# M6_GPOI_V4_1_after_labelling.net
KiCad netlist of a schematic drawn in EAGLE
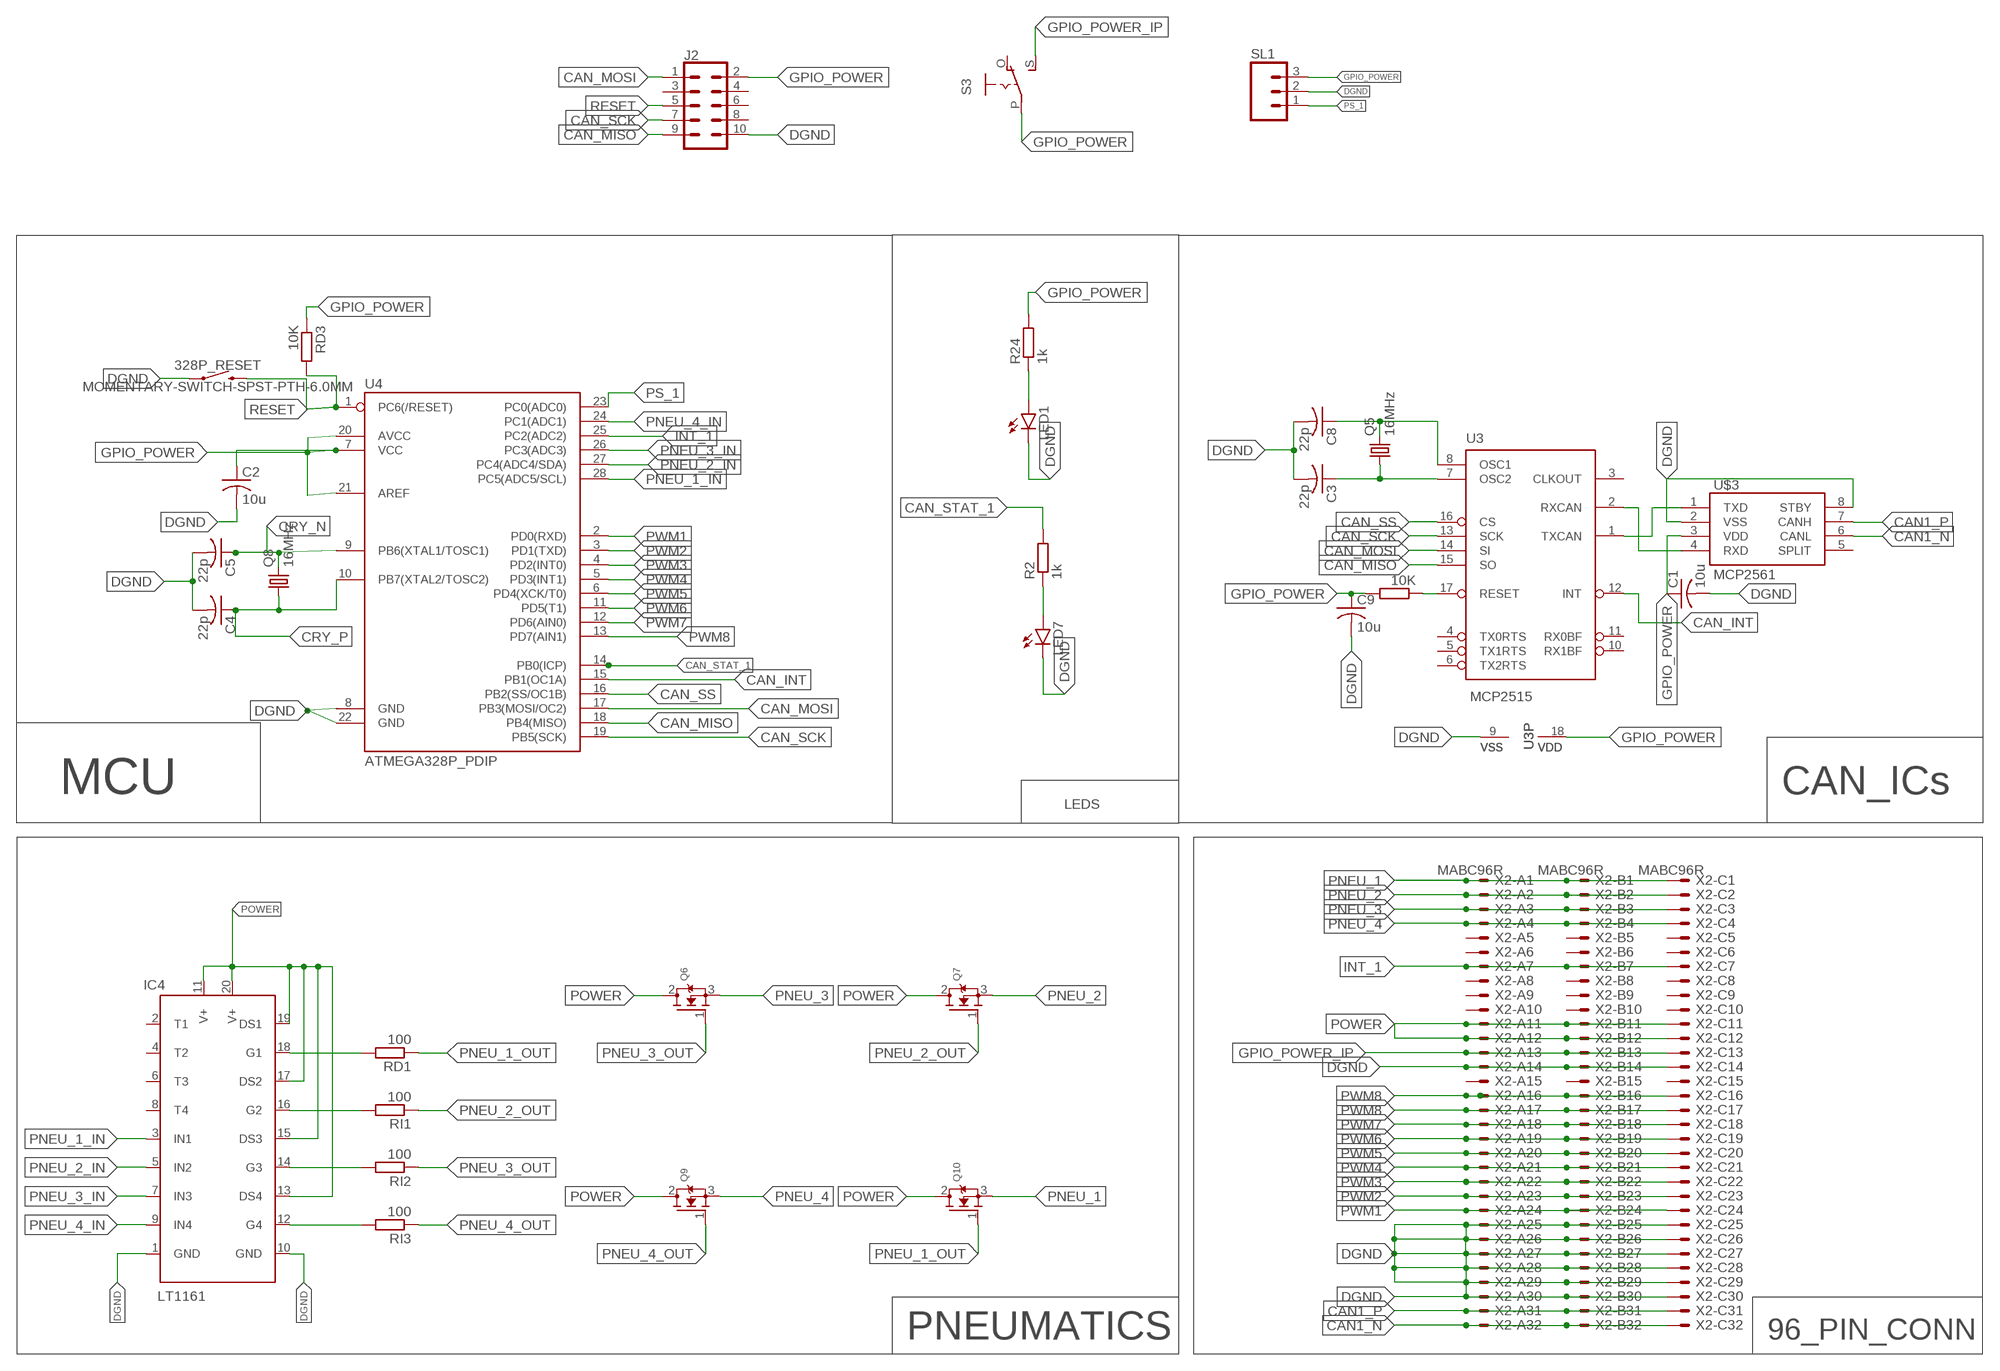
[diagram p0: schematic, sheet 1]

(export (version "E")
  (design (tool "Eeschema 10.0.6"))
  (components
    (comp (ref "328P_RESET")
      (value "MOMENTARY-SWITCH-SPST-PTH-6.0MM")
      (footprint "eagle-import:TACTILE_SWITCH_PTH_6.0MM")
      (libsource (lib "eagle-import") (part "MOMENTARY-SWITCH-SPST-PTH-6.0MM"))
    )
    (comp (ref "C1")
      (value "10u")
      (footprint "eagle-import:C025-050X050")
      (libsource (lib "eagle-import") (part "C-US025-050X050"))
    )
    (comp (ref "C2")
      (value "10u")
      (footprint "eagle-import:C025-050X050")
      (libsource (lib "eagle-import") (part "C-US025-050X050"))
    )
    (comp (ref "C3")
      (value "22p")
      (footprint "eagle-import:C025-024X044")
      (libsource (lib "eagle-import") (part "resistor_C-US025-024X044"))
    )
    (comp (ref "C4")
      (value "22p")
      (footprint "eagle-import:C025-024X044")
      (libsource (lib "eagle-import") (part "resistor_348_C-US025-024X044"))
    )
    (comp (ref "C5")
      (value "22p")
      (footprint "eagle-import:C025-024X044")
      (libsource (lib "eagle-import") (part "resistor_348_C-US025-024X044"))
    )
    (comp (ref "C8")
      (value "22p")
      (footprint "eagle-import:C025-024X044")
      (libsource (lib "eagle-import") (part "resistor_C-US025-024X044"))
    )
    (comp (ref "C9")
      (value "10u")
      (footprint "eagle-import:C025-050X050")
      (libsource (lib "eagle-import") (part "C-US025-050X050"))
    )
    (comp (ref "IC4")
      (value "LT1161")
      (footprint "eagle-import:ROBOSUB_LINEAR-TECHNOLOGY_LT1161_QUAD-HIGH-SIDE-MOSFET-DRIVER_SO20")
      (fields (field (name "MF") "INTERSIL") (field (name "MPN") "HIP4086ABZ"))
      (libsource (lib "eagle-import") (part "ROBOSUB_LINEAR-TECHNOLOGY_LT1161_QUAD-HIGH-SIDE-MOSFET-DRIVER_LT1161-SO20SW"))
    )
    (comp (ref "J2")
      (value "CONN_05X2SHD")
      (footprint "eagle-import:2X5-SHROUDED")
      (libsource (lib "eagle-import") (part "CONN_05X2SHD"))
    )
    (comp (ref "LED1")
      (value "LEDCHIPLED_0805")
      (footprint "eagle-import:CHIPLED_0805")
      (libsource (lib "eagle-import") (part "LEDCHIPLED_0805"))
    )
    (comp (ref "LED7")
      (value "LEDCHIPLED_0805")
      (footprint "eagle-import:CHIPLED_0805")
      (libsource (lib "eagle-import") (part "LEDCHIPLED_0805"))
    )
    (comp (ref "Q5")
      (value "16MHz")
      (footprint "eagle-import:HC49_S")
      (libsource (lib "eagle-import") (part "CRYSTALHC49S"))
    )
    (comp (ref "Q6")
      (value "MOSFET-NGDS_TO220V")
      (footprint "eagle-import:TO220V")
      (libsource (lib "eagle-import") (part "MOSFET-NGDS_TO220V"))
    )
    (comp (ref "Q7")
      (value "MOSFET-NGDS_TO220V")
      (footprint "eagle-import:TO220V")
      (libsource (lib "eagle-import") (part "MOSFET-NGDS_TO220V"))
    )
    (comp (ref "Q8")
      (value "16MHz")
      (footprint "eagle-import:HC49_S")
      (libsource (lib "eagle-import") (part "CRYSTALHC49S"))
    )
    (comp (ref "Q9")
      (value "MOSFET-NGDS_TO220V")
      (footprint "eagle-import:TO220V")
      (libsource (lib "eagle-import") (part "MOSFET-NGDS_TO220V"))
    )
    (comp (ref "Q10")
      (value "MOSFET-NGDS_TO220V")
      (footprint "eagle-import:TO220V")
      (libsource (lib "eagle-import") (part "MOSFET-NGDS_TO220V"))
    )
    (comp (ref "R2")
      (value "1k")
      (footprint "eagle-import:M0805")
      (libsource (lib "eagle-import") (part "R-EU_M0805"))
    )
    (comp (ref "R24")
      (value "1k")
      (footprint "eagle-import:M0805")
      (libsource (lib "eagle-import") (part "R-EU_M0805"))
    )
    (comp (ref "RD1")
      (value "100")
      (footprint "eagle-import:M0805")
      (libsource (lib "eagle-import") (part "R-EU_M0805"))
    )
    (comp (ref "RD2")
      (value "10K")
      (footprint "eagle-import:M0805")
      (libsource (lib "eagle-import") (part "R-EU_M0805"))
    )
    (comp (ref "RD3")
      (value "10K")
      (footprint "eagle-import:M0805")
      (libsource (lib "eagle-import") (part "R-EU_M0805"))
    )
    (comp (ref "RI1")
      (value "100")
      (footprint "eagle-import:M0805")
      (libsource (lib "eagle-import") (part "R-EU_M0805"))
    )
    (comp (ref "RI2")
      (value "100")
      (footprint "eagle-import:M0805")
      (libsource (lib "eagle-import") (part "R-EU_M0805"))
    )
    (comp (ref "RI3")
      (value "100")
      (footprint "eagle-import:M0805")
      (libsource (lib "eagle-import") (part "R-EU_M0805"))
    )
    (comp (ref "S3")
      (value "EG1218S")
      (footprint "eagle-import:EG1218")
      (libsource (lib "eagle-import") (part "EG1218S"))
    )
    (comp (ref "SL1")
      (value "MA03")
      (footprint "eagle-import:03P")
      (libsource (lib "eagle-import") (part "MA03"))
    )
    (comp (ref "U$3")
      (value "MCP2561")
      (footprint "eagle-import:DIP08")
      (libsource (lib "eagle-import") (part "MCP2561"))
    )
    (comp (ref "U3")
      (value "MCP2515")
      (footprint "eagle-import:DIP18")
      (libsource (lib "eagle-import") (part "MCP2515(MCP2510)P"))
    )
    (comp (ref "U4")
      (value "ATMEGA328P_PDIP")
      (footprint "eagle-import:DIL28-3")
      (libsource (lib "eagle-import") (part "ATMEGA328P_PDIP"))
    )
    (comp (ref "X2")
      (value "MABC96R")
      (footprint "eagle-import:MABC96R")
      (fields (field (name "OC_FARNELL") "unknown"))
      (libsource (lib "eagle-import") (part "MABC96R"))
    )
  )
  (nets
    (net (code "1") (name "CAN1_N") (class "Default")
      (node (ref "U$3") (pin "6") (pinfunction "CANL_6") (pintype "bidirectional"))
      (node (ref "X2") (pin "A32") (pinfunction "S_A32") (pintype "passive"))
      (node (ref "X2") (pin "B32") (pinfunction "S_B32") (pintype "passive"))
      (node (ref "X2") (pin "C32") (pinfunction "S_C32") (pintype "passive"))
    )
    (net (code "2") (name "CAN1_P") (class "Default")
      (node (ref "U$3") (pin "7") (pinfunction "CANH_7") (pintype "bidirectional"))
      (node (ref "X2") (pin "A31") (pinfunction "S_A31") (pintype "passive"))
      (node (ref "X2") (pin "B31") (pinfunction "S_B31") (pintype "passive"))
      (node (ref "X2") (pin "C31") (pinfunction "S_C31") (pintype "passive"))
    )
    (net (code "3") (name "CAN_INT") (class "Default")
      (node (ref "U3") (pin "12") (pinfunction "INT_12") (pintype "output"))
      (node (ref "U4") (pin "15") (pinfunction "PB1(OC1A)_15") (pintype "bidirectional"))
    )
    (net (code "4") (name "CAN_MISO") (class "Default")
      (node (ref "J2") (pin "9") (pinfunction "9_9") (pintype "passive"))
      (node (ref "U3") (pin "15") (pinfunction "SO_15") (pintype "output"))
      (node (ref "U4") (pin "18") (pinfunction "PB4(MISO)_18") (pintype "bidirectional"))
    )
    (net (code "5") (name "CAN_MOSI") (class "Default")
      (node (ref "J2") (pin "1") (pinfunction "1_1") (pintype "passive"))
      (node (ref "U3") (pin "14") (pinfunction "SI_14") (pintype "input"))
      (node (ref "U4") (pin "17") (pinfunction "PB3(MOSI/OC2)_17") (pintype "bidirectional"))
    )
    (net (code "6") (name "CAN_SCK") (class "Default")
      (node (ref "J2") (pin "7") (pinfunction "7_7") (pintype "passive"))
      (node (ref "U3") (pin "13") (pinfunction "SCK_13") (pintype "input"))
      (node (ref "U4") (pin "19") (pinfunction "PB5(SCK)_19") (pintype "bidirectional"))
    )
    (net (code "7") (name "CAN_SS") (class "Default")
      (node (ref "U3") (pin "16") (pinfunction "CS_16") (pintype "input"))
      (node (ref "U4") (pin "16") (pinfunction "PB2(SS/OC1B)_16") (pintype "bidirectional"))
    )
    (net (code "8") (name "CAN_STAT_1") (class "Default")
      (node (ref "R2") (pin "2") (pinfunction "2_2") (pintype "passive"))
      (node (ref "U4") (pin "14") (pinfunction "PB0(ICP)_14") (pintype "bidirectional"))
    )
    (net (code "9") (name "CRY_N") (class "Default")
      (node (ref "C5") (pin "1") (pinfunction "1_1") (pintype "passive"))
      (node (ref "Q8") (pin "2") (pinfunction "2_2") (pintype "passive"))
      (node (ref "U4") (pin "9") (pinfunction "PB6(XTAL1/TOSC1)_9") (pintype "bidirectional"))
    )
    (net (code "10") (name "CRY_P") (class "Default")
      (node (ref "C4") (pin "1") (pinfunction "1_1") (pintype "passive"))
      (node (ref "Q8") (pin "1") (pinfunction "1_1") (pintype "passive"))
      (node (ref "U4") (pin "10") (pinfunction "PB7(XTAL2/TOSC2)_10") (pintype "bidirectional"))
    )
    (net (code "11") (name "DGND") (class "Default")
      (node (ref "328P_RESET") (pin "1") (pinfunction "1_1") (pintype "passive"))
      (node (ref "C1") (pin "2") (pinfunction "2_2") (pintype "passive"))
      (node (ref "C2") (pin "2") (pinfunction "2_2") (pintype "passive"))
      (node (ref "C3") (pin "2") (pinfunction "2_2") (pintype "passive"))
      (node (ref "C4") (pin "2") (pinfunction "2_2") (pintype "passive"))
      (node (ref "C5") (pin "2") (pinfunction "2_2") (pintype "passive"))
      (node (ref "C8") (pin "2") (pinfunction "2_2") (pintype "passive"))
      (node (ref "C9") (pin "2") (pinfunction "2_2") (pintype "passive"))
      (node (ref "IC4") (pin "1") (pinfunction "GND_1") (pintype "power_in"))
      (node (ref "IC4") (pin "10") (pinfunction "GND_10") (pintype "power_in"))
      (node (ref "J2") (pin "10") (pinfunction "10_10") (pintype "passive"))
      (node (ref "LED1") (pin "C") (pinfunction "C_C") (pintype "passive"))
      (node (ref "LED7") (pin "C") (pinfunction "C_C") (pintype "passive"))
      (node (ref "SL1") (pin "2") (pinfunction "2_2") (pintype "passive"))
      (node (ref "U$3") (pin "2") (pinfunction "VSS_2") (pintype "bidirectional"))
      (node (ref "U$3") (pin "8") (pinfunction "STBY_8") (pintype "bidirectional"))
      (node (ref "U3") (pin "9") (pinfunction "VSS_9") (pintype "power_in"))
      (node (ref "U4") (pin "22") (pinfunction "GND_22") (pintype "bidirectional"))
      (node (ref "U4") (pin "8") (pinfunction "GND_8") (pintype "bidirectional"))
      (node (ref "X2") (pin "A14") (pinfunction "S_A14") (pintype "passive"))
      (node (ref "X2") (pin "A25") (pinfunction "S_A25") (pintype "passive"))
      (node (ref "X2") (pin "A26") (pinfunction "S_A26") (pintype "passive"))
      (node (ref "X2") (pin "A27") (pinfunction "S_A27") (pintype "passive"))
      (node (ref "X2") (pin "A28") (pinfunction "S_A28") (pintype "passive"))
      (node (ref "X2") (pin "A29") (pinfunction "S_A29") (pintype "passive"))
      (node (ref "X2") (pin "A30") (pinfunction "S_A30") (pintype "passive"))
      (node (ref "X2") (pin "B14") (pinfunction "S_B14") (pintype "passive"))
      (node (ref "X2") (pin "B25") (pinfunction "S_B25") (pintype "passive"))
      (node (ref "X2") (pin "B26") (pinfunction "S_B26") (pintype "passive"))
      (node (ref "X2") (pin "B27") (pinfunction "S_B27") (pintype "passive"))
      (node (ref "X2") (pin "B28") (pinfunction "S_B28") (pintype "passive"))
      (node (ref "X2") (pin "B29") (pinfunction "S_B29") (pintype "passive"))
      (node (ref "X2") (pin "B30") (pinfunction "S_B30") (pintype "passive"))
      (node (ref "X2") (pin "C14") (pinfunction "S_C14") (pintype "passive"))
      (node (ref "X2") (pin "C25") (pinfunction "S_C25") (pintype "passive"))
      (node (ref "X2") (pin "C26") (pinfunction "S_C26") (pintype "passive"))
      (node (ref "X2") (pin "C27") (pinfunction "S_C27") (pintype "passive"))
      (node (ref "X2") (pin "C28") (pinfunction "S_C28") (pintype "passive"))
      (node (ref "X2") (pin "C29") (pinfunction "S_C29") (pintype "passive"))
      (node (ref "X2") (pin "C30") (pinfunction "S_C30") (pintype "passive"))
    )
    (net (code "12") (name "GPIO_POWER") (class "Default")
      (node (ref "C1") (pin "1") (pinfunction "1_1") (pintype "passive"))
      (node (ref "C2") (pin "1") (pinfunction "1_1") (pintype "passive"))
      (node (ref "C9") (pin "1") (pinfunction "1_1") (pintype "passive"))
      (node (ref "J2") (pin "2") (pinfunction "2_2") (pintype "passive"))
      (node (ref "R24") (pin "2") (pinfunction "2_2") (pintype "passive"))
      (node (ref "RD2") (pin "2") (pinfunction "2_2") (pintype "passive"))
      (node (ref "RD3") (pin "1") (pinfunction "1_1") (pintype "passive"))
      (node (ref "S3") (pin "P") (pinfunction "P_P") (pintype "passive"))
      (node (ref "SL1") (pin "3") (pinfunction "3_3") (pintype "passive"))
      (node (ref "U$3") (pin "3") (pinfunction "VDD_3") (pintype "bidirectional"))
      (node (ref "U3") (pin "18") (pinfunction "VDD_18") (pintype "power_in"))
      (node (ref "U4") (pin "20") (pinfunction "AVCC_20") (pintype "bidirectional"))
      (node (ref "U4") (pin "21") (pinfunction "AREF_21") (pintype "bidirectional"))
      (node (ref "U4") (pin "7") (pinfunction "VCC_7") (pintype "bidirectional"))
    )
    (net (code "13") (name "GPIO_POWER_IP") (class "Default")
      (node (ref "S3") (pin "S") (pinfunction "S_S") (pintype "passive"))
      (node (ref "X2") (pin "A13") (pinfunction "S_A13") (pintype "passive"))
      (node (ref "X2") (pin "B13") (pinfunction "S_B13") (pintype "passive"))
      (node (ref "X2") (pin "C13") (pinfunction "S_C13") (pintype "passive"))
    )
    (net (code "14") (name "INT_1") (class "Default")
      (node (ref "U4") (pin "25") (pinfunction "PC2(ADC2)_25") (pintype "bidirectional"))
      (node (ref "X2") (pin "A7") (pinfunction "S_A7") (pintype "passive"))
      (node (ref "X2") (pin "B7") (pinfunction "S_B7") (pintype "passive"))
      (node (ref "X2") (pin "C7") (pinfunction "S_C7") (pintype "passive"))
    )
    (net (code "15") (name "Net-(IC4-G1)") (class "Default")
      (node (ref "IC4") (pin "18") (pinfunction "G1_18") (pintype "output"))
      (node (ref "RD1") (pin "2") (pinfunction "2_2") (pintype "passive"))
    )
    (net (code "16") (name "Net-(IC4-G2)") (class "Default")
      (node (ref "IC4") (pin "16") (pinfunction "G2_16") (pintype "output"))
      (node (ref "RI1") (pin "2") (pinfunction "2_2") (pintype "passive"))
    )
    (net (code "17") (name "Net-(IC4-G3)") (class "Default")
      (node (ref "IC4") (pin "14") (pinfunction "G3_14") (pintype "output"))
      (node (ref "RI2") (pin "2") (pinfunction "2_2") (pintype "passive"))
    )
    (net (code "18") (name "Net-(IC4-G4)") (class "Default")
      (node (ref "IC4") (pin "12") (pinfunction "G4_12") (pintype "output"))
      (node (ref "RI3") (pin "2") (pinfunction "2_2") (pintype "passive"))
    )
    (net (code "19") (name "Net-(LED1-PadA)") (class "Default")
      (node (ref "LED1") (pin "A") (pinfunction "A_A") (pintype "passive"))
      (node (ref "R24") (pin "1") (pinfunction "1_1") (pintype "passive"))
    )
    (net (code "20") (name "Net-(LED7-PadA)") (class "Default")
      (node (ref "LED7") (pin "A") (pinfunction "A_A") (pintype "passive"))
      (node (ref "R2") (pin "1") (pinfunction "1_1") (pintype "passive"))
    )
    (net (code "21") (name "Net-(U$3-RXD)") (class "Default")
      (node (ref "U$3") (pin "4") (pinfunction "RXD_4") (pintype "bidirectional"))
      (node (ref "U3") (pin "2") (pinfunction "RXCAN_2") (pintype "input"))
    )
    (net (code "22") (name "Net-(U$3-TXD)") (class "Default")
      (node (ref "U$3") (pin "1") (pinfunction "TXD_1") (pintype "bidirectional"))
      (node (ref "U3") (pin "1") (pinfunction "TXCAN_1") (pintype "output"))
    )
    (net (code "23") (name "Net-(U3A-OSC1)") (class "Default")
      (node (ref "C8") (pin "1") (pinfunction "1_1") (pintype "passive"))
      (node (ref "Q5") (pin "2") (pinfunction "2_2") (pintype "passive"))
      (node (ref "U3") (pin "8") (pinfunction "OSC1_8") (pintype "input"))
    )
    (net (code "24") (name "Net-(U3A-OSC2)") (class "Default")
      (node (ref "C3") (pin "1") (pinfunction "1_1") (pintype "passive"))
      (node (ref "Q5") (pin "1") (pinfunction "1_1") (pintype "passive"))
      (node (ref "U3") (pin "7") (pinfunction "OSC2_7") (pintype "output"))
    )
    (net (code "25") (name "Net-(U3A-RESET)") (class "Default")
      (node (ref "RD2") (pin "1") (pinfunction "1_1") (pintype "passive"))
      (node (ref "U3") (pin "17") (pinfunction "RESET_17") (pintype "input"))
    )
    (net (code "26") (name "PNEU_1") (class "Default")
      (node (ref "Q10") (pin "3") (pinfunction "S_3") (pintype "bidirectional"))
      (node (ref "X2") (pin "A1") (pinfunction "S_A1") (pintype "passive"))
      (node (ref "X2") (pin "B1") (pinfunction "S_B1") (pintype "passive"))
      (node (ref "X2") (pin "C1") (pinfunction "S_C1") (pintype "passive"))
    )
    (net (code "27") (name "PNEU_1_IN") (class "Default")
      (node (ref "IC4") (pin "3") (pinfunction "IN1_3") (pintype "bidirectional"))
      (node (ref "U4") (pin "28") (pinfunction "PC5(ADC5/SCL)_28") (pintype "bidirectional"))
    )
    (net (code "28") (name "PNEU_1_OUT") (class "Default")
      (node (ref "Q10") (pin "1") (pinfunction "G_1") (pintype "bidirectional"))
      (node (ref "RD1") (pin "1") (pinfunction "1_1") (pintype "passive"))
    )
    (net (code "29") (name "PNEU_2") (class "Default")
      (node (ref "Q7") (pin "3") (pinfunction "S_3") (pintype "bidirectional"))
      (node (ref "X2") (pin "A2") (pinfunction "S_A2") (pintype "passive"))
      (node (ref "X2") (pin "B2") (pinfunction "S_B2") (pintype "passive"))
      (node (ref "X2") (pin "C2") (pinfunction "S_C2") (pintype "passive"))
    )
    (net (code "30") (name "PNEU_2_IN") (class "Default")
      (node (ref "IC4") (pin "5") (pinfunction "IN2_5") (pintype "input"))
      (node (ref "U4") (pin "27") (pinfunction "PC4(ADC4/SDA)_27") (pintype "bidirectional"))
    )
    (net (code "31") (name "PNEU_2_OUT") (class "Default")
      (node (ref "Q7") (pin "1") (pinfunction "G_1") (pintype "bidirectional"))
      (node (ref "RI1") (pin "1") (pinfunction "1_1") (pintype "passive"))
    )
    (net (code "32") (name "PNEU_3") (class "Default")
      (node (ref "Q6") (pin "3") (pinfunction "S_3") (pintype "bidirectional"))
      (node (ref "X2") (pin "A3") (pinfunction "S_A3") (pintype "passive"))
      (node (ref "X2") (pin "B3") (pinfunction "S_B3") (pintype "passive"))
      (node (ref "X2") (pin "C3") (pinfunction "S_C3") (pintype "passive"))
    )
    (net (code "33") (name "PNEU_3_IN") (class "Default")
      (node (ref "IC4") (pin "7") (pinfunction "IN3_7") (pintype "input"))
      (node (ref "U4") (pin "26") (pinfunction "PC3(ADC3)_26") (pintype "bidirectional"))
    )
    (net (code "34") (name "PNEU_3_OUT") (class "Default")
      (node (ref "Q6") (pin "1") (pinfunction "G_1") (pintype "bidirectional"))
      (node (ref "RI2") (pin "1") (pinfunction "1_1") (pintype "passive"))
    )
    (net (code "35") (name "PNEU_4") (class "Default")
      (node (ref "Q9") (pin "3") (pinfunction "S_3") (pintype "bidirectional"))
      (node (ref "X2") (pin "A4") (pinfunction "S_A4") (pintype "passive"))
      (node (ref "X2") (pin "B4") (pinfunction "S_B4") (pintype "passive"))
      (node (ref "X2") (pin "C4") (pinfunction "S_C4") (pintype "passive"))
    )
    (net (code "36") (name "PNEU_4_IN") (class "Default")
      (node (ref "IC4") (pin "9") (pinfunction "IN4_9") (pintype "input"))
      (node (ref "U4") (pin "24") (pinfunction "PC1(ADC1)_24") (pintype "bidirectional"))
    )
    (net (code "37") (name "PNEU_4_OUT") (class "Default")
      (node (ref "Q9") (pin "1") (pinfunction "G_1") (pintype "bidirectional"))
      (node (ref "RI3") (pin "1") (pinfunction "1_1") (pintype "passive"))
    )
    (net (code "38") (name "POWER") (class "Default")
      (node (ref "IC4") (pin "11") (pinfunction "V+_11") (pintype "power_in"))
      (node (ref "IC4") (pin "13") (pinfunction "DS4_13") (pintype "input"))
      (node (ref "IC4") (pin "15") (pinfunction "DS3_15") (pintype "input"))
      (node (ref "IC4") (pin "17") (pinfunction "DS2_17") (pintype "input"))
      (node (ref "IC4") (pin "19") (pinfunction "DS1_19") (pintype "input"))
      (node (ref "IC4") (pin "20") (pinfunction "V+_20") (pintype "power_in"))
      (node (ref "Q10") (pin "2") (pinfunction "D_2") (pintype "bidirectional"))
      (node (ref "Q6") (pin "2") (pinfunction "D_2") (pintype "bidirectional"))
      (node (ref "Q7") (pin "2") (pinfunction "D_2") (pintype "bidirectional"))
      (node (ref "Q9") (pin "2") (pinfunction "D_2") (pintype "bidirectional"))
      (node (ref "X2") (pin "A11") (pinfunction "S_A11") (pintype "passive"))
      (node (ref "X2") (pin "A12") (pinfunction "S_A12") (pintype "passive"))
      (node (ref "X2") (pin "B11") (pinfunction "S_B11") (pintype "passive"))
      (node (ref "X2") (pin "B12") (pinfunction "S_B12") (pintype "passive"))
      (node (ref "X2") (pin "C11") (pinfunction "S_C11") (pintype "passive"))
      (node (ref "X2") (pin "C12") (pinfunction "S_C12") (pintype "passive"))
    )
    (net (code "39") (name "PS_1") (class "Default")
      (node (ref "SL1") (pin "1") (pinfunction "1_1") (pintype "passive"))
      (node (ref "U4") (pin "23") (pinfunction "PC0(ADC0)_23") (pintype "bidirectional"))
    )
    (net (code "40") (name "PWM1") (class "Default")
      (node (ref "U4") (pin "2") (pinfunction "PD0(RXD)_2") (pintype "bidirectional"))
      (node (ref "X2") (pin "A24") (pinfunction "S_A24") (pintype "passive"))
      (node (ref "X2") (pin "B24") (pinfunction "S_B24") (pintype "passive"))
      (node (ref "X2") (pin "C24") (pinfunction "S_C24") (pintype "passive"))
    )
    (net (code "41") (name "PWM2") (class "Default")
      (node (ref "U4") (pin "3") (pinfunction "PD1(TXD)_3") (pintype "bidirectional"))
      (node (ref "X2") (pin "A23") (pinfunction "S_A23") (pintype "passive"))
      (node (ref "X2") (pin "B23") (pinfunction "S_B23") (pintype "passive"))
      (node (ref "X2") (pin "C23") (pinfunction "S_C23") (pintype "passive"))
    )
    (net (code "42") (name "PWM3") (class "Default")
      (node (ref "U4") (pin "4") (pinfunction "PD2(INT0)_4") (pintype "bidirectional"))
      (node (ref "X2") (pin "A22") (pinfunction "S_A22") (pintype "passive"))
      (node (ref "X2") (pin "B22") (pinfunction "S_B22") (pintype "passive"))
      (node (ref "X2") (pin "C22") (pinfunction "S_C22") (pintype "passive"))
    )
    (net (code "43") (name "PWM4") (class "Default")
      (node (ref "U4") (pin "5") (pinfunction "PD3(INT1)_5") (pintype "bidirectional"))
      (node (ref "X2") (pin "A21") (pinfunction "S_A21") (pintype "passive"))
      (node (ref "X2") (pin "B21") (pinfunction "S_B21") (pintype "passive"))
      (node (ref "X2") (pin "C21") (pinfunction "S_C21") (pintype "passive"))
    )
    (net (code "44") (name "PWM5") (class "Default")
      (node (ref "U4") (pin "6") (pinfunction "PD4(XCK/T0)_6") (pintype "bidirectional"))
      (node (ref "X2") (pin "A20") (pinfunction "S_A20") (pintype "passive"))
      (node (ref "X2") (pin "B20") (pinfunction "S_B20") (pintype "passive"))
      (node (ref "X2") (pin "C20") (pinfunction "S_C20") (pintype "passive"))
    )
    (net (code "45") (name "PWM6") (class "Default")
      (node (ref "U4") (pin "11") (pinfunction "PD5(T1)_11") (pintype "bidirectional"))
      (node (ref "X2") (pin "A19") (pinfunction "S_A19") (pintype "passive"))
      (node (ref "X2") (pin "B19") (pinfunction "S_B19") (pintype "passive"))
      (node (ref "X2") (pin "C19") (pinfunction "S_C19") (pintype "passive"))
    )
    (net (code "46") (name "PWM7") (class "Default")
      (node (ref "U4") (pin "12") (pinfunction "PD6(AIN0)_12") (pintype "bidirectional"))
      (node (ref "X2") (pin "A18") (pinfunction "S_A18") (pintype "passive"))
      (node (ref "X2") (pin "B18") (pinfunction "S_B18") (pintype "passive"))
      (node (ref "X2") (pin "C18") (pinfunction "S_C18") (pintype "passive"))
    )
    (net (code "47") (name "PWM8") (class "Default")
      (node (ref "U4") (pin "13") (pinfunction "PD7(AIN1)_13") (pintype "bidirectional"))
      (node (ref "X2") (pin "A16") (pinfunction "S_A16") (pintype "passive"))
      (node (ref "X2") (pin "A17") (pinfunction "S_A17") (pintype "passive"))
      (node (ref "X2") (pin "B16") (pinfunction "S_B16") (pintype "passive"))
      (node (ref "X2") (pin "B17") (pinfunction "S_B17") (pintype "passive"))
      (node (ref "X2") (pin "C16") (pinfunction "S_C16") (pintype "passive"))
      (node (ref "X2") (pin "C17") (pinfunction "S_C17") (pintype "passive"))
    )
    (net (code "48") (name "RESET") (class "Default")
      (node (ref "328P_RESET") (pin "3") (pinfunction "2_3") (pintype "passive"))
      (node (ref "J2") (pin "5") (pinfunction "5_5") (pintype "passive"))
      (node (ref "RD3") (pin "2") (pinfunction "2_2") (pintype "passive"))
      (node (ref "U4") (pin "1") (pinfunction "PC6(/RESET)_1") (pintype "bidirectional"))
    )
    (net (code "49") (name "unconnected-(IC4-T1-Pad2)") (class "Default")
      (node (ref "IC4") (pin "2") (pinfunction "T1_2") (pintype "bidirectional"))
    )
    (net (code "50") (name "unconnected-(IC4-T2-Pad4)") (class "Default")
      (node (ref "IC4") (pin "4") (pinfunction "T2_4") (pintype "bidirectional"))
    )
    (net (code "51") (name "unconnected-(IC4-T3-Pad6)") (class "Default")
      (node (ref "IC4") (pin "6") (pinfunction "T3_6") (pintype "bidirectional"))
    )
    (net (code "52") (name "unconnected-(IC4-T4-Pad8)") (class "Default")
      (node (ref "IC4") (pin "8") (pinfunction "T4_8") (pintype "bidirectional"))
    )
    (net (code "53") (name "unconnected-(J2-Pad3)") (class "Default")
      (node (ref "J2") (pin "3") (pinfunction "3_3") (pintype "passive"))
    )
    (net (code "54") (name "unconnected-(J2-Pad4)") (class "Default")
      (node (ref "J2") (pin "4") (pinfunction "4_4") (pintype "passive"))
    )
    (net (code "55") (name "unconnected-(J2-Pad6)") (class "Default")
      (node (ref "J2") (pin "6") (pinfunction "6_6") (pintype "passive"))
    )
    (net (code "56") (name "unconnected-(J2-Pad8)") (class "Default")
      (node (ref "J2") (pin "8") (pinfunction "8_8") (pintype "passive"))
    )
    (net (code "57") (name "unconnected-(S3-PadO)") (class "Default")
      (node (ref "S3") (pin "O") (pinfunction "O_O") (pintype "passive"))
    )
    (net (code "58") (name "unconnected-(U$3-SPLIT-Pad5)") (class "Default")
      (node (ref "U$3") (pin "5") (pinfunction "SPLIT_5") (pintype "bidirectional"))
    )
    (net (code "59") (name "unconnected-(U3A-CLKOUT-Pad3)") (class "Default")
      (node (ref "U3") (pin "3") (pinfunction "CLKOUT_3") (pintype "output"))
    )
    (net (code "60") (name "unconnected-(U3A-RX0BF-Pad11)") (class "Default")
      (node (ref "U3") (pin "11") (pinfunction "RX0BF_11") (pintype "output"))
    )
    (net (code "61") (name "unconnected-(U3A-RX1BF-Pad10)") (class "Default")
      (node (ref "U3") (pin "10") (pinfunction "RX1BF_10") (pintype "output"))
    )
    (net (code "62") (name "unconnected-(U3A-TX0RTS-Pad4)") (class "Default")
      (node (ref "U3") (pin "4") (pinfunction "TX0RTS_4") (pintype "input"))
    )
    (net (code "63") (name "unconnected-(U3A-TX1RTS-Pad5)") (class "Default")
      (node (ref "U3") (pin "5") (pinfunction "TX1RTS_5") (pintype "input"))
    )
    (net (code "64") (name "unconnected-(U3A-TX2RTS-Pad6)") (class "Default")
      (node (ref "U3") (pin "6") (pinfunction "TX2RTS_6") (pintype "input"))
    )
    (net (code "65") (name "unconnected-(X2AB-S-PadA5)") (class "Default")
      (node (ref "X2") (pin "A5") (pinfunction "S_A5") (pintype "passive"))
    )
    (net (code "66") (name "unconnected-(X2AC-S-PadA6)") (class "Default")
      (node (ref "X2") (pin "A6") (pinfunction "S_A6") (pintype "passive"))
    )
    (net (code "67") (name "unconnected-(X2AE-S-PadA8)") (class "Default")
      (node (ref "X2") (pin "A8") (pinfunction "S_A8") (pintype "passive"))
    )
    (net (code "68") (name "unconnected-(X2AF-S-PadA9)") (class "Default")
      (node (ref "X2") (pin "A9") (pinfunction "S_A9") (pintype "passive"))
    )
    (net (code "69") (name "unconnected-(X2AH-S-PadB10)") (class "Default")
      (node (ref "X2") (pin "B10") (pinfunction "S_B10") (pintype "passive"))
    )
    (net (code "70") (name "unconnected-(X2AM-S-PadB15)") (class "Default")
      (node (ref "X2") (pin "B15") (pinfunction "S_B15") (pintype "passive"))
    )
    (net (code "71") (name "unconnected-(X2B-S-PadA10)") (class "Default")
      (node (ref "X2") (pin "A10") (pinfunction "S_A10") (pintype "passive"))
    )
    (net (code "72") (name "unconnected-(X2BH-S-PadB5)") (class "Default")
      (node (ref "X2") (pin "B5") (pinfunction "S_B5") (pintype "passive"))
    )
    (net (code "73") (name "unconnected-(X2BI-S-PadB6)") (class "Default")
      (node (ref "X2") (pin "B6") (pinfunction "S_B6") (pintype "passive"))
    )
    (net (code "74") (name "unconnected-(X2BK-S-PadB8)") (class "Default")
      (node (ref "X2") (pin "B8") (pinfunction "S_B8") (pintype "passive"))
    )
    (net (code "75") (name "unconnected-(X2BL-S-PadB9)") (class "Default")
      (node (ref "X2") (pin "B9") (pinfunction "S_B9") (pintype "passive"))
    )
    (net (code "76") (name "unconnected-(X2BN-S-PadC10)") (class "Default")
      (node (ref "X2") (pin "C10") (pinfunction "S_C10") (pintype "passive"))
    )
    (net (code "77") (name "unconnected-(X2BS-S-PadC15)") (class "Default")
      (node (ref "X2") (pin "C15") (pinfunction "S_C15") (pintype "passive"))
    )
    (net (code "78") (name "unconnected-(X2CN-S-PadC5)") (class "Default")
      (node (ref "X2") (pin "C5") (pinfunction "S_C5") (pintype "passive"))
    )
    (net (code "79") (name "unconnected-(X2CO-S-PadC6)") (class "Default")
      (node (ref "X2") (pin "C6") (pinfunction "S_C6") (pintype "passive"))
    )
    (net (code "80") (name "unconnected-(X2CQ-S-PadC8)") (class "Default")
      (node (ref "X2") (pin "C8") (pinfunction "S_C8") (pintype "passive"))
    )
    (net (code "81") (name "unconnected-(X2CR-S-PadC9)") (class "Default")
      (node (ref "X2") (pin "C9") (pinfunction "S_C9") (pintype "passive"))
    )
    (net (code "82") (name "unconnected-(X2G-S-PadA15)") (class "Default")
      (node (ref "X2") (pin "A15") (pinfunction "S_A15") (pintype "passive"))
    )
  )
)
